# in4_control_v1_0_revA.net
KiCad netlist of a schematic drawn in EAGLE
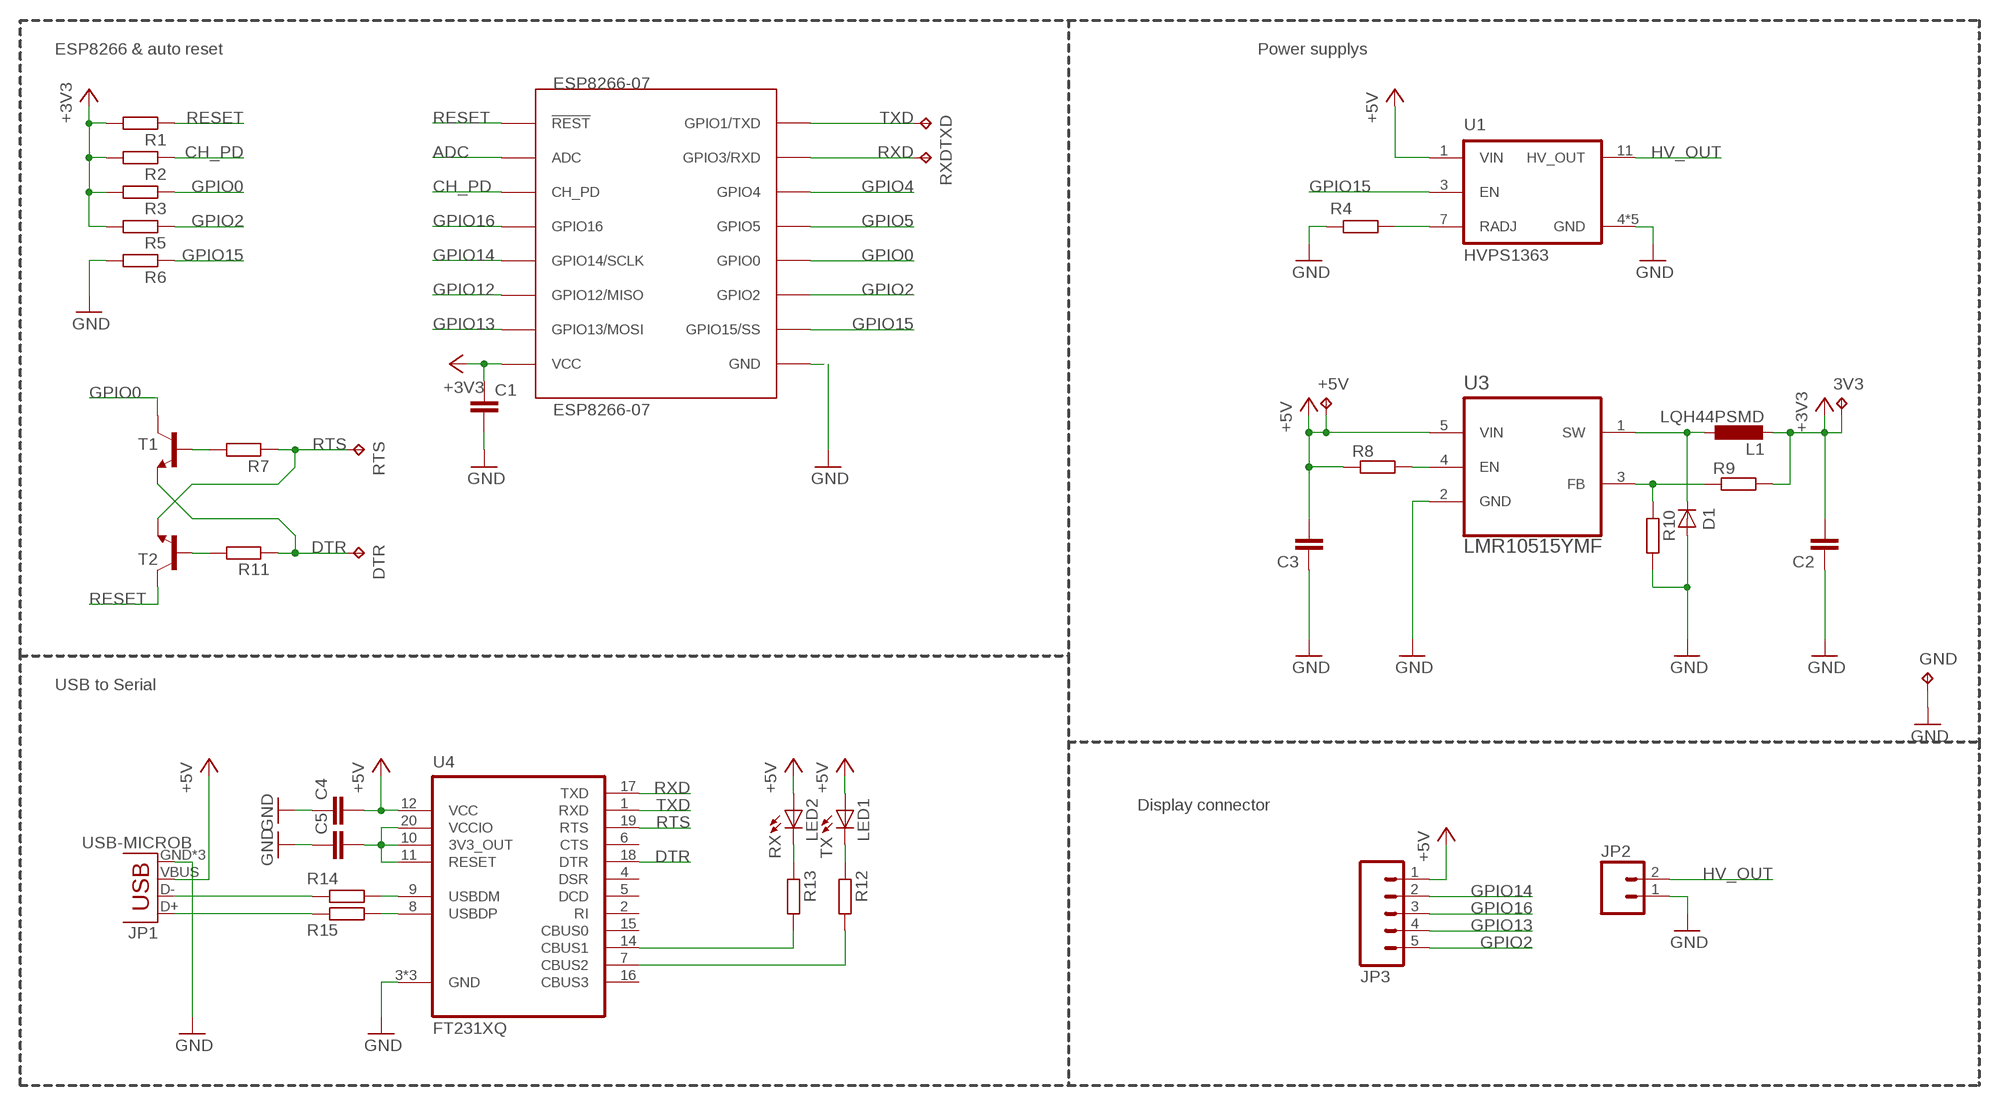
[diagram p0: schematic, sheet 1]

(export (version "E")
  (design (tool "Eeschema 10.0.6"))
  (components
    (comp (ref "+5V")
      (value "TPTP17R")
      (footprint "eagle-import:TP17R")
      (libsource (lib "eagle-import") (part "TPTP17R"))
    )
    (comp (ref "3V3")
      (value "TPTP15R")
      (footprint "eagle-import:TP15R")
      (libsource (lib "eagle-import") (part "TPTP15R"))
    )
    (comp (ref "C1")
      (value "C-EUC0805")
      (footprint "eagle-import:C0805")
      (libsource (lib "eagle-import") (part "resistor_C-EUC0805"))
    )
    (comp (ref "C2")
      (value "C-EUC0805")
      (footprint "eagle-import:C0805")
      (libsource (lib "eagle-import") (part "C-EUC0805"))
    )
    (comp (ref "C3")
      (value "C-EUC0805")
      (footprint "eagle-import:C0805")
      (libsource (lib "eagle-import") (part "C-EUC0805"))
    )
    (comp (ref "C4")
      (value "C-EUC0603")
      (footprint "eagle-import:C0603")
      (libsource (lib "eagle-import") (part "resistor_C-EUC0603"))
    )
    (comp (ref "C5")
      (value "C-EUC0603")
      (footprint "eagle-import:C0603")
      (libsource (lib "eagle-import") (part "resistor_C-EUC0603"))
    )
    (comp (ref "D1")
      (value "DIODE-SOD-123")
      (footprint "eagle-import:SOD-123")
      (libsource (lib "eagle-import") (part "DIODE-SOD-123"))
    )
    (comp (ref "DTR")
      (value "TPTP17R")
      (footprint "eagle-import:TP17R")
      (libsource (lib "eagle-import") (part "TPTP17R"))
    )
    (comp (ref "ESP8266-07")
      (value "ESP8266-07")
      (footprint "eagle-import:ESP07")
      (libsource (lib "eagle-import") (part "ESP8266-07"))
    )
    (comp (ref "GND")
      (value "TPTP17R")
      (footprint "eagle-import:TP17R")
      (libsource (lib "eagle-import") (part "TPTP17R"))
    )
    (comp (ref "JP1")
      (value "USB-MICROB")
      (footprint "eagle-import:USB-MICROB")
      (libsource (lib "eagle-import") (part "USB-MICROB"))
    )
    (comp (ref "JP2")
      (value "M021X02_NO_SILK")
      (footprint "eagle-import:1X02_NO_SILK")
      (libsource (lib "eagle-import") (part "M021X02_NO_SILK"))
    )
    (comp (ref "JP3")
      (value "M05PTH")
      (footprint "eagle-import:1X05")
      (libsource (lib "eagle-import") (part "M05PTH"))
    )
    (comp (ref "L1")
      (value "LQH44PSMD")
      (footprint "eagle-import:1515")
      (libsource (lib "eagle-import") (part "LQH44PSMD"))
    )
    (comp (ref "LED1")
      (value "TX")
      (footprint "eagle-import:CHIP-LED0603")
      (libsource (lib "eagle-import") (part "LEDCHIP-LED0603"))
    )
    (comp (ref "LED2")
      (value "RX")
      (footprint "eagle-import:CHIP-LED0603")
      (libsource (lib "eagle-import") (part "LEDCHIP-LED0603"))
    )
    (comp (ref "R1")
      (value "R-EU_R0603")
      (footprint "eagle-import:R0603")
      (libsource (lib "eagle-import") (part "R-EU_R0603"))
    )
    (comp (ref "R2")
      (value "R-EU_R0603")
      (footprint "eagle-import:R0603")
      (libsource (lib "eagle-import") (part "R-EU_R0603"))
    )
    (comp (ref "R3")
      (value "R-EU_R0603")
      (footprint "eagle-import:R0603")
      (libsource (lib "eagle-import") (part "R-EU_R0603"))
    )
    (comp (ref "R4")
      (value "R-EU_R0603")
      (footprint "eagle-import:R0603")
      (libsource (lib "eagle-import") (part "R-EU_R0603"))
    )
    (comp (ref "R5")
      (value "R-EU_R0603")
      (footprint "eagle-import:R0603")
      (libsource (lib "eagle-import") (part "R-EU_R0603"))
    )
    (comp (ref "R6")
      (value "R-EU_R0603")
      (footprint "eagle-import:R0603")
      (libsource (lib "eagle-import") (part "R-EU_R0603"))
    )
    (comp (ref "R7")
      (value "R-EU_R0603")
      (footprint "eagle-import:R0603")
      (libsource (lib "eagle-import") (part "R-EU_R0603"))
    )
    (comp (ref "R8")
      (value "R-EU_R0603")
      (footprint "eagle-import:R0603")
      (libsource (lib "eagle-import") (part "R-EU_R0603"))
    )
    (comp (ref "R9")
      (value "R-EU_R0603")
      (footprint "eagle-import:R0603")
      (libsource (lib "eagle-import") (part "R-EU_R0603"))
    )
    (comp (ref "R10")
      (value "R-EU_R0603")
      (footprint "eagle-import:R0603")
      (libsource (lib "eagle-import") (part "R-EU_R0603"))
    )
    (comp (ref "R11")
      (value "R-EU_R0603")
      (footprint "eagle-import:R0603")
      (libsource (lib "eagle-import") (part "R-EU_R0603"))
    )
    (comp (ref "R12")
      (value "R-EU_R0603")
      (footprint "eagle-import:R0603")
      (libsource (lib "eagle-import") (part "R-EU_R0603"))
    )
    (comp (ref "R13")
      (value "R-EU_R0603")
      (footprint "eagle-import:R0603")
      (libsource (lib "eagle-import") (part "R-EU_R0603"))
    )
    (comp (ref "R14")
      (value "R-EU_R0603")
      (footprint "eagle-import:R0603")
      (libsource (lib "eagle-import") (part "R-EU_R0603"))
    )
    (comp (ref "R15")
      (value "R-EU_R0603")
      (footprint "eagle-import:R0603")
      (libsource (lib "eagle-import") (part "R-EU_R0603"))
    )
    (comp (ref "RTS")
      (value "TPTP17R")
      (footprint "eagle-import:TP17R")
      (libsource (lib "eagle-import") (part "TPTP17R"))
    )
    (comp (ref "RXD")
      (value "TPTP17R")
      (footprint "eagle-import:TP17R")
      (libsource (lib "eagle-import") (part "TPTP17R"))
    )
    (comp (ref "T1")
      (value "MMBT3904LT1-NPN-SOT23-BEC")
      (footprint "eagle-import:SOT23-BEC")
      (libsource (lib "eagle-import") (part "-NPN-SOT23-BECMMBT3904LT1"))
    )
    (comp (ref "T2")
      (value "MMBT3904LT1-NPN-SOT23-BEC")
      (footprint "eagle-import:SOT23-BEC")
      (libsource (lib "eagle-import") (part "-NPN-SOT23-BECMMBT3904LT1"))
    )
    (comp (ref "TXD")
      (value "TPTP17R")
      (footprint "eagle-import:TP17R")
      (libsource (lib "eagle-import") (part "TPTP17R"))
    )
    (comp (ref "U1")
      (value "HVPS1363")
      (footprint "eagle-import:HVPS-1363")
      (libsource (lib "eagle-import") (part "HVPS1363"))
    )
    (comp (ref "U3")
      (value "LMR10515YMF")
      (footprint "eagle-import:SOT95P290X145-5N")
      (libsource (lib "eagle-import") (part "LMR10515YMF"))
    )
    (comp (ref "U4")
      (value "FT231XQ")
      (footprint "eagle-import:QFN-20")
      (libsource (lib "eagle-import") (part "FT231XQ"))
    )
  )
  (nets
    (net (code "1") (name "+3V3") (class "Default")
      (node (ref "3V3") (pin "TP") (pinfunction "TP_TP") (pintype "input"))
      (node (ref "C1") (pin "1") (pinfunction "1_1") (pintype "passive"))
      (node (ref "C2") (pin "2") (pinfunction "2_2") (pintype "passive"))
      (node (ref "ESP8266-07") (pin "VCC") (pinfunction "VCC_VCC") (pintype "power_in"))
      (node (ref "L1") (pin "2") (pinfunction "2_2") (pintype "passive"))
      (node (ref "R1") (pin "2") (pinfunction "2_2") (pintype "passive"))
      (node (ref "R2") (pin "2") (pinfunction "2_2") (pintype "passive"))
      (node (ref "R3") (pin "2") (pinfunction "2_2") (pintype "passive"))
      (node (ref "R5") (pin "2") (pinfunction "2_2") (pintype "passive"))
      (node (ref "R9") (pin "2") (pinfunction "2_2") (pintype "passive"))
    )
    (net (code "2") (name "+5V") (class "Default")
      (node (ref "+5V") (pin "TP") (pinfunction "TP_TP") (pintype "input"))
      (node (ref "C3") (pin "2") (pinfunction "2_2") (pintype "passive"))
      (node (ref "C4") (pin "2") (pinfunction "2_2") (pintype "passive"))
      (node (ref "JP1") (pin "VBUS") (pinfunction "VBUS_VBUS") (pintype "bidirectional"))
      (node (ref "JP3") (pin "1") (pinfunction "1_1") (pintype "passive"))
      (node (ref "LED1") (pin "A") (pinfunction "A_A") (pintype "passive"))
      (node (ref "LED2") (pin "A") (pinfunction "A_A") (pintype "passive"))
      (node (ref "R8") (pin "1") (pinfunction "1_1") (pintype "passive"))
      (node (ref "U1") (pin "1") (pinfunction "VIN_1") (pintype "bidirectional"))
      (node (ref "U3") (pin "5") (pinfunction "VIN_5") (pintype "power_in"))
      (node (ref "U4") (pin "12") (pinfunction "VCC_12") (pintype "bidirectional"))
    )
    (net (code "3") (name "/ADC") (class "Default")
      (node (ref "ESP8266-07") (pin "ADC") (pinfunction "ADC_ADC") (pintype "bidirectional"))
    )
    (net (code "4") (name "/CH_PD") (class "Default")
      (node (ref "ESP8266-07") (pin "CH_PD") (pinfunction "CH_PD_CH_PD") (pintype "input"))
      (node (ref "R2") (pin "1") (pinfunction "1_1") (pintype "passive"))
    )
    (net (code "5") (name "/DTR") (class "Default")
      (node (ref "DTR") (pin "TP") (pinfunction "TP_TP") (pintype "input"))
      (node (ref "R11") (pin "1") (pinfunction "1_1") (pintype "passive"))
      (node (ref "T1") (pin "E") (pinfunction "E_E") (pintype "passive"))
      (node (ref "U4") (pin "18") (pinfunction "DTR_18") (pintype "bidirectional"))
    )
    (net (code "6") (name "/GPIO0") (class "Default")
      (node (ref "ESP8266-07") (pin "GPIO0") (pinfunction "GPIO0_GPIO0") (pintype "bidirectional"))
      (node (ref "R3") (pin "1") (pinfunction "1_1") (pintype "passive"))
      (node (ref "T1") (pin "C") (pinfunction "C_C") (pintype "passive"))
    )
    (net (code "7") (name "/GPIO2") (class "Default")
      (node (ref "ESP8266-07") (pin "GPIO2") (pinfunction "GPIO2_GPIO2") (pintype "bidirectional"))
      (node (ref "JP3") (pin "5") (pinfunction "5_5") (pintype "passive"))
      (node (ref "R5") (pin "1") (pinfunction "1_1") (pintype "passive"))
    )
    (net (code "8") (name "/GPIO4") (class "Default")
      (node (ref "ESP8266-07") (pin "GPIO4") (pinfunction "GPIO4_GPIO4") (pintype "bidirectional"))
    )
    (net (code "9") (name "/GPIO5") (class "Default")
      (node (ref "ESP8266-07") (pin "GPIO5") (pinfunction "GPIO5_GPIO5") (pintype "bidirectional"))
    )
    (net (code "10") (name "/GPIO12") (class "Default")
      (node (ref "ESP8266-07") (pin "GPIO12") (pinfunction "GPIO12/MISO_GPIO12") (pintype "bidirectional"))
    )
    (net (code "11") (name "/GPIO13") (class "Default")
      (node (ref "ESP8266-07") (pin "GPIO13") (pinfunction "GPIO13/MOSI_GPIO13") (pintype "bidirectional"))
      (node (ref "JP3") (pin "4") (pinfunction "4_4") (pintype "passive"))
    )
    (net (code "12") (name "/GPIO14") (class "Default")
      (node (ref "ESP8266-07") (pin "GPIO14") (pinfunction "GPIO14/SCLK_GPIO14") (pintype "bidirectional"))
      (node (ref "JP3") (pin "2") (pinfunction "2_2") (pintype "passive"))
    )
    (net (code "13") (name "/GPIO15") (class "Default")
      (node (ref "ESP8266-07") (pin "GPIO15") (pinfunction "GPIO15/SS_GPIO15") (pintype "input"))
      (node (ref "R6") (pin "1") (pinfunction "1_1") (pintype "passive"))
      (node (ref "U1") (pin "3") (pinfunction "EN_3") (pintype "bidirectional"))
    )
    (net (code "14") (name "/GPIO16") (class "Default")
      (node (ref "ESP8266-07") (pin "GPIO16") (pinfunction "GPIO16_GPIO16") (pintype "bidirectional"))
      (node (ref "JP3") (pin "3") (pinfunction "3_3") (pintype "passive"))
    )
    (net (code "15") (name "/HV_OUT") (class "Default")
      (node (ref "JP2") (pin "2") (pinfunction "2_2") (pintype "passive"))
      (node (ref "U1") (pin "11") (pinfunction "HV_OUT_11") (pintype "bidirectional"))
    )
    (net (code "16") (name "/RESET") (class "Default")
      (node (ref "ESP8266-07") (pin "REST") (pinfunction "~{REST}_REST") (pintype "bidirectional"))
      (node (ref "R1") (pin "1") (pinfunction "1_1") (pintype "passive"))
      (node (ref "T2") (pin "C") (pinfunction "C_C") (pintype "passive"))
    )
    (net (code "17") (name "/RTS") (class "Default")
      (node (ref "R7") (pin "1") (pinfunction "1_1") (pintype "passive"))
      (node (ref "RTS") (pin "TP") (pinfunction "TP_TP") (pintype "input"))
      (node (ref "T2") (pin "E") (pinfunction "E_E") (pintype "passive"))
      (node (ref "U4") (pin "19") (pinfunction "RTS_19") (pintype "bidirectional"))
    )
    (net (code "18") (name "/RXD") (class "Default")
      (node (ref "ESP8266-07") (pin "RXD") (pinfunction "GPIO3/RXD_RXD") (pintype "input"))
      (node (ref "RXD") (pin "TP") (pinfunction "TP_TP") (pintype "input"))
      (node (ref "U4") (pin "17") (pinfunction "TXD_17") (pintype "bidirectional"))
    )
    (net (code "19") (name "/TXD") (class "Default")
      (node (ref "ESP8266-07") (pin "TXD") (pinfunction "GPIO1/TXD_TXD") (pintype "output"))
      (node (ref "TXD") (pin "TP") (pinfunction "TP_TP") (pintype "input"))
      (node (ref "U4") (pin "1") (pinfunction "RXD_1") (pintype "bidirectional"))
    )
    (net (code "20") (name "GND") (class "Default")
      (node (ref "C1") (pin "2") (pinfunction "2_2") (pintype "passive"))
      (node (ref "C2") (pin "1") (pinfunction "1_1") (pintype "passive"))
      (node (ref "C3") (pin "1") (pinfunction "1_1") (pintype "passive"))
      (node (ref "C4") (pin "1") (pinfunction "1_1") (pintype "passive"))
      (node (ref "C5") (pin "1") (pinfunction "1_1") (pintype "passive"))
      (node (ref "D1") (pin "A") (pinfunction "A_A") (pintype "passive"))
      (node (ref "ESP8266-07") (pin "GND") (pinfunction "GND_GND") (pintype "power_in"))
      (node (ref "GND") (pin "TP") (pinfunction "TP_TP") (pintype "input"))
      (node (ref "JP1") (pin "GND") (pinfunction "GND_GND") (pintype "bidirectional"))
      (node (ref "JP1") (pin "MT1") (pinfunction "GND_MT1") (pintype "bidirectional"))
      (node (ref "JP1") (pin "MT2") (pinfunction "GND_MT2") (pintype "bidirectional"))
      (node (ref "JP2") (pin "1") (pinfunction "1_1") (pintype "passive"))
      (node (ref "R10") (pin "2") (pinfunction "2_2") (pintype "passive"))
      (node (ref "R4") (pin "2") (pinfunction "2_2") (pintype "passive"))
      (node (ref "R6") (pin "2") (pinfunction "2_2") (pintype "passive"))
      (node (ref "U1") (pin "10") (pinfunction "GND_10") (pintype "bidirectional"))
      (node (ref "U1") (pin "4") (pinfunction "GND_4") (pintype "bidirectional"))
      (node (ref "U1") (pin "6") (pinfunction "GND_6") (pintype "bidirectional"))
      (node (ref "U1") (pin "8") (pinfunction "GND_8") (pintype "bidirectional"))
      (node (ref "U1") (pin "9") (pinfunction "GND_9") (pintype "bidirectional"))
      (node (ref "U3") (pin "2") (pinfunction "GND_2") (pintype "passive"))
      (node (ref "U4") (pin "13") (pinfunction "GND_13") (pintype "bidirectional"))
      (node (ref "U4") (pin "21") (pinfunction "GND_21") (pintype "bidirectional"))
      (node (ref "U4") (pin "3") (pinfunction "GND_3") (pintype "bidirectional"))
    )
    (net (code "21") (name "Net-(JP1-PadD+)") (class "Default")
      (node (ref "JP1") (pin "D+") (pinfunction "D+_D+") (pintype "bidirectional"))
      (node (ref "R15") (pin "2") (pinfunction "2_2") (pintype "passive"))
    )
    (net (code "22") (name "Net-(JP1-PadD-)") (class "Default")
      (node (ref "JP1") (pin "D-") (pinfunction "D-_D-") (pintype "bidirectional"))
      (node (ref "R14") (pin "2") (pinfunction "2_2") (pintype "passive"))
    )
    (net (code "23") (name "Net-(LED1-PadC)") (class "Default")
      (node (ref "LED1") (pin "C") (pinfunction "C_C") (pintype "passive"))
      (node (ref "R12") (pin "1") (pinfunction "1_1") (pintype "passive"))
    )
    (net (code "24") (name "Net-(LED2-PadC)") (class "Default")
      (node (ref "LED2") (pin "C") (pinfunction "C_C") (pintype "passive"))
      (node (ref "R13") (pin "1") (pinfunction "1_1") (pintype "passive"))
    )
    (net (code "25") (name "Net-(R7-Pad2)") (class "Default")
      (node (ref "R7") (pin "2") (pinfunction "2_2") (pintype "passive"))
      (node (ref "T1") (pin "B") (pinfunction "B_B") (pintype "passive"))
    )
    (net (code "26") (name "Net-(R11-Pad2)") (class "Default")
      (node (ref "R11") (pin "2") (pinfunction "2_2") (pintype "passive"))
      (node (ref "T2") (pin "B") (pinfunction "B_B") (pintype "passive"))
    )
    (net (code "27") (name "Net-(U1-RADJ)") (class "Default")
      (node (ref "R4") (pin "1") (pinfunction "1_1") (pintype "passive"))
      (node (ref "U1") (pin "7") (pinfunction "RADJ_7") (pintype "bidirectional"))
    )
    (net (code "28") (name "Net-(U3-EN)") (class "Default")
      (node (ref "R8") (pin "2") (pinfunction "2_2") (pintype "passive"))
      (node (ref "U3") (pin "4") (pinfunction "EN_4") (pintype "input"))
    )
    (net (code "29") (name "Net-(U3-FB)") (class "Default")
      (node (ref "R10") (pin "1") (pinfunction "1_1") (pintype "passive"))
      (node (ref "R9") (pin "1") (pinfunction "1_1") (pintype "passive"))
      (node (ref "U3") (pin "3") (pinfunction "FB_3") (pintype "input"))
    )
    (net (code "30") (name "Net-(U3-SW)") (class "Default")
      (node (ref "D1") (pin "C") (pinfunction "C_C") (pintype "passive"))
      (node (ref "L1") (pin "1") (pinfunction "1_1") (pintype "passive"))
      (node (ref "U3") (pin "1") (pinfunction "SW_1") (pintype "passive"))
    )
    (net (code "31") (name "Net-(U4-3V3_OUT)") (class "Default")
      (node (ref "C5") (pin "2") (pinfunction "2_2") (pintype "passive"))
      (node (ref "U4") (pin "10") (pinfunction "3V3_OUT_10") (pintype "bidirectional"))
      (node (ref "U4") (pin "11") (pinfunction "RESET_11") (pintype "bidirectional"))
      (node (ref "U4") (pin "20") (pinfunction "VCCIO_20") (pintype "bidirectional"))
    )
    (net (code "32") (name "Net-(U4-CBUS1)") (class "Default")
      (node (ref "R13") (pin "2") (pinfunction "2_2") (pintype "passive"))
      (node (ref "U4") (pin "14") (pinfunction "CBUS1_14") (pintype "bidirectional"))
    )
    (net (code "33") (name "Net-(U4-CBUS2)") (class "Default")
      (node (ref "R12") (pin "2") (pinfunction "2_2") (pintype "passive"))
      (node (ref "U4") (pin "7") (pinfunction "CBUS2_7") (pintype "bidirectional"))
    )
    (net (code "34") (name "Net-(U4-USBDM)") (class "Default")
      (node (ref "R14") (pin "1") (pinfunction "1_1") (pintype "passive"))
      (node (ref "U4") (pin "9") (pinfunction "USBDM_9") (pintype "bidirectional"))
    )
    (net (code "35") (name "Net-(U4-USBDP)") (class "Default")
      (node (ref "R15") (pin "1") (pinfunction "1_1") (pintype "passive"))
      (node (ref "U4") (pin "8") (pinfunction "USBDP_8") (pintype "bidirectional"))
    )
    (net (code "36") (name "unconnected-(U4-CBUS0-Pad15)") (class "Default")
      (node (ref "U4") (pin "15") (pinfunction "CBUS0_15") (pintype "bidirectional"))
    )
    (net (code "37") (name "unconnected-(U4-CBUS3-Pad16)") (class "Default")
      (node (ref "U4") (pin "16") (pinfunction "CBUS3_16") (pintype "bidirectional"))
    )
    (net (code "38") (name "unconnected-(U4-CTS-Pad6)") (class "Default")
      (node (ref "U4") (pin "6") (pinfunction "CTS_6") (pintype "bidirectional"))
    )
    (net (code "39") (name "unconnected-(U4-DCD-Pad5)") (class "Default")
      (node (ref "U4") (pin "5") (pinfunction "DCD_5") (pintype "bidirectional"))
    )
    (net (code "40") (name "unconnected-(U4-DSR-Pad4)") (class "Default")
      (node (ref "U4") (pin "4") (pinfunction "DSR_4") (pintype "bidirectional"))
    )
    (net (code "41") (name "unconnected-(U4-RI-Pad2)") (class "Default")
      (node (ref "U4") (pin "2") (pinfunction "RI_2") (pintype "bidirectional"))
    )
  )
)
